# Superbot_hbridge.net
KiCad netlist of a schematic drawn in Altium Designer
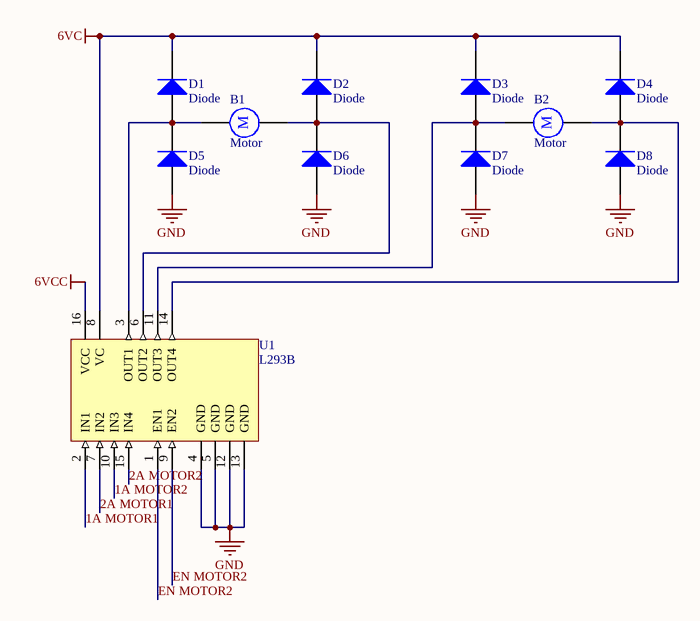
[diagram p0: Superbot_hbridge.SchDoc]

(export (version "E")
  (design (tool "Eeschema 10.0.6"))
  (components
    (comp (ref "B1")
      (value "Motor")
      (footprint "RB5-10.5")
      (description "Motor, General Kind")
      (fields (field (name "PUBLISHER") "Altium Limited"))
      (libsource (lib "Miscellaneous Devices") (part "Motor"))
    )
    (comp (ref "B2")
      (value "Motor")
      (footprint "RB5-10.5")
      (description "Motor, General Kind")
      (fields (field (name "PUBLISHER") "Altium Limited"))
      (libsource (lib "Miscellaneous Devices") (part "Motor"))
    )
    (comp (ref "D1")
      (value "Diode")
      (footprint "SMC")
      (description "Default Diode")
      (fields (field (name "PUBLISHER") "Altium Limited"))
      (libsource (lib "Miscellaneous Devices") (part "Diode"))
    )
    (comp (ref "D2")
      (value "Diode")
      (footprint "SMC")
      (description "Default Diode")
      (fields (field (name "PUBLISHER") "Altium Limited"))
      (libsource (lib "Miscellaneous Devices") (part "Diode"))
    )
    (comp (ref "D3")
      (value "Diode")
      (footprint "SMC")
      (description "Default Diode")
      (fields (field (name "PUBLISHER") "Altium Limited"))
      (libsource (lib "Miscellaneous Devices") (part "Diode"))
    )
    (comp (ref "D4")
      (value "Diode")
      (footprint "SMC")
      (description "Default Diode")
      (fields (field (name "PUBLISHER") "Altium Limited"))
      (libsource (lib "Miscellaneous Devices") (part "Diode"))
    )
    (comp (ref "D5")
      (value "Diode")
      (footprint "SMC")
      (description "Default Diode")
      (fields (field (name "PUBLISHER") "Altium Limited"))
      (libsource (lib "Miscellaneous Devices") (part "Diode"))
    )
    (comp (ref "D6")
      (value "Diode")
      (footprint "SMC")
      (description "Default Diode")
      (fields (field (name "PUBLISHER") "Altium Limited"))
      (libsource (lib "Miscellaneous Devices") (part "Diode"))
    )
    (comp (ref "D7")
      (value "Diode")
      (footprint "SMC")
      (description "Default Diode")
      (fields (field (name "PUBLISHER") "Altium Limited"))
      (libsource (lib "Miscellaneous Devices") (part "Diode"))
    )
    (comp (ref "D8")
      (value "Diode")
      (footprint "SMC")
      (description "Default Diode")
      (fields (field (name "PUBLISHER") "Altium Limited"))
      (libsource (lib "Miscellaneous Devices") (part "Diode"))
    )
    (comp (ref "U1")
      (value "L293B")
      (footprint "DIP16")
      (description "Push-Pull Four Channel Drivers")
      (fields (field (name "PUBLISHER") "Altium Limited"))
      (libsource (lib "ST Interface DC & Stepper Motor Controller") (part "L293B"))
    )
  )
  (nets
    (net (code "1") (name "/1A MOTOR1") (class "Default")
      (node (ref "U1") (pin "2") (pinfunction "IN1_2") (pintype "input"))
    )
    (net (code "2") (name "/1A MOTOR2") (class "Default")
      (node (ref "U1") (pin "10") (pinfunction "IN3_10") (pintype "input"))
    )
    (net (code "3") (name "/2A MOTOR1") (class "Default")
      (node (ref "U1") (pin "7") (pinfunction "IN2_7") (pintype "input"))
    )
    (net (code "4") (name "/2A MOTOR2") (class "Default")
      (node (ref "U1") (pin "15") (pinfunction "IN4_15") (pintype "input"))
    )
    (net (code "5") (name "/EN MOTOR2") (class "Default")
      (node (ref "U1") (pin "1") (pinfunction "EN1_1") (pintype "input"))
      (node (ref "U1") (pin "9") (pinfunction "EN2_9") (pintype "input"))
    )
    (net (code "6") (name "6VC") (class "Default")
      (node (ref "D1") (pin "2") (pinfunction "K_2") (pintype "passive"))
      (node (ref "D2") (pin "2") (pinfunction "K_2") (pintype "passive"))
      (node (ref "D3") (pin "2") (pinfunction "K_2") (pintype "passive"))
      (node (ref "D4") (pin "2") (pinfunction "K_2") (pintype "passive"))
      (node (ref "U1") (pin "8") (pinfunction "VC_8") (pintype "power_in"))
    )
    (net (code "7") (name "6VCC") (class "Default")
      (node (ref "U1") (pin "16") (pinfunction "VCC_16") (pintype "power_in"))
    )
    (net (code "8") (name "GND") (class "Default")
      (node (ref "D5") (pin "1") (pinfunction "A_1") (pintype "passive"))
      (node (ref "D6") (pin "1") (pinfunction "A_1") (pintype "passive"))
      (node (ref "D7") (pin "1") (pinfunction "A_1") (pintype "passive"))
      (node (ref "D8") (pin "1") (pinfunction "A_1") (pintype "passive"))
      (node (ref "U1") (pin "12") (pinfunction "GND_12") (pintype "power_in"))
      (node (ref "U1") (pin "13") (pinfunction "GND_13") (pintype "power_in"))
      (node (ref "U1") (pin "4") (pinfunction "GND_4") (pintype "power_in"))
      (node (ref "U1") (pin "5") (pinfunction "GND_5") (pintype "power_in"))
    )
    (net (code "9") (name "Net-(D1-A)") (class "Default")
      (node (ref "B1") (pin "1") (pinfunction "1_1") (pintype "passive"))
      (node (ref "D1") (pin "1") (pinfunction "A_1") (pintype "passive"))
      (node (ref "D5") (pin "2") (pinfunction "K_2") (pintype "passive"))
      (node (ref "U1") (pin "3") (pinfunction "OUT1_3") (pintype "output"))
    )
    (net (code "10") (name "Net-(D2-A)") (class "Default")
      (node (ref "B1") (pin "2") (pinfunction "2_2") (pintype "passive"))
      (node (ref "D2") (pin "1") (pinfunction "A_1") (pintype "passive"))
      (node (ref "D6") (pin "2") (pinfunction "K_2") (pintype "passive"))
      (node (ref "U1") (pin "6") (pinfunction "OUT2_6") (pintype "output"))
    )
    (net (code "11") (name "Net-(D3-A)") (class "Default")
      (node (ref "B2") (pin "1") (pinfunction "1_1") (pintype "passive"))
      (node (ref "D3") (pin "1") (pinfunction "A_1") (pintype "passive"))
      (node (ref "D7") (pin "2") (pinfunction "K_2") (pintype "passive"))
      (node (ref "U1") (pin "11") (pinfunction "OUT3_11") (pintype "output"))
    )
    (net (code "12") (name "Net-(D4-A)") (class "Default")
      (node (ref "B2") (pin "2") (pinfunction "2_2") (pintype "passive"))
      (node (ref "D4") (pin "1") (pinfunction "A_1") (pintype "passive"))
      (node (ref "D8") (pin "2") (pinfunction "K_2") (pintype "passive"))
      (node (ref "U1") (pin "14") (pinfunction "OUT4_14") (pintype "output"))
    )
  )
)
